# Sheet2.net
KiCad netlist of a schematic drawn in Altium Designer
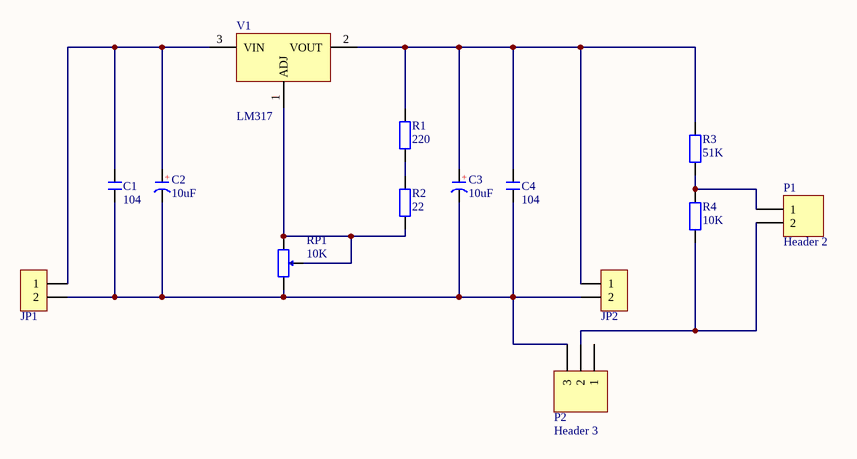
[diagram p0: Sheet2.SchDoc]

(export (version "E")
  (design (tool "Eeschema 10.0.6"))
  (components
    (comp (ref "C1")
      (value "104")
      (footprint "C 0805_M")
      (description "贴片电容")
      (libsource (lib "01 - 电容-电阻-电感") (part "C"))
    )
    (comp (ref "C2")
      (value "10uF")
      (footprint "CAP 2.0*5*11")
      (description "直插电解电容")
      (libsource (lib "01 - 电容-电阻-电感") (part "CE"))
    )
    (comp (ref "C3")
      (value "10uF")
      (footprint "CAP 2.0*5*11")
      (description "直插电解电容")
      (libsource (lib "01 - 电容-电阻-电感") (part "CE"))
    )
    (comp (ref "C4")
      (value "104")
      (footprint "C 0805_M")
      (description "贴片电容")
      (libsource (lib "01 - 电容-电阻-电感") (part "C"))
    )
    (comp (ref "JP1")
      (value "HDR-1X2")
      (footprint "KF2EDGK5.0-LI-2P")
      (description "2P接插件")
      (libsource (lib "") (part "Header 2_1"))
    )
    (comp (ref "JP2")
      (value "HDR-1X2")
      (footprint "KF2EDGK5.0-LI-2P")
      (description "2P接插件")
      (libsource (lib "21 - 接插件-脚距5.0mm") (part "Header 2"))
    )
    (comp (ref "P1")
      (value "Header 2")
      (footprint "HDR1X2")
      (description "Header, 2-Pin")
      (fields (field (name "PUBLISHER") "Altium Limited"))
      (libsource (lib "Miscellaneous Connectors") (part "Header 2"))
    )
    (comp (ref "P2")
      (value "Header 3")
      (footprint "HDR1X3")
      (description "Header, 3-Pin")
      (fields (field (name "PUBLISHER") "Altium Limited"))
      (libsource (lib "Miscellaneous Connectors") (part "Header 3"))
    )
    (comp (ref "R1")
      (value "220")
      (footprint "R 0805_M")
      (description "贴片电阻")
      (libsource (lib "01 - 电容-电阻-电感") (part "R"))
    )
    (comp (ref "R2")
      (value "22")
      (footprint "R 0805_M")
      (description "贴片电阻")
      (libsource (lib "01 - 电容-电阻-电感") (part "R"))
    )
    (comp (ref "R3")
      (value "51K")
      (footprint "R 0805_M")
      (description "贴片电阻")
      (libsource (lib "01 - 电容-电阻-电感") (part "R"))
    )
    (comp (ref "R4")
      (value "10K")
      (footprint "R 0805_M")
      (description "贴片电阻")
      (libsource (lib "01 - 电容-电阻-电感") (part "R"))
    )
    (comp (ref "RP1")
      (value "10K")
      (footprint "3296W")
      (description "单联电位器")
      (libsource (lib "01 - 电容-电阻-电感") (part "RP"))
    )
    (comp (ref "V1")
      (value "LM317")
      (footprint "TO220A")
      (description "可调线性稳压芯片")
      (libsource (lib "08 - 稳压芯片-电源管理芯片") (part "LM317"))
    )
  )
  (nets
    (net (code "1") (name "Net-(C2-A)") (class "Default")
      (node (ref "C1") (pin "2") (pinfunction "2_2") (pintype "passive"))
      (node (ref "C2") (pin "1") (pinfunction "A_1") (pintype "passive"))
      (node (ref "JP1") (pin "1") (pinfunction "1_1") (pintype "passive"))
      (node (ref "V1") (pin "3") (pinfunction "VIN_3") (pintype "passive"))
    )
    (net (code "2") (name "Net-(C2-K)") (class "Default")
      (node (ref "C1") (pin "1") (pinfunction "1_1") (pintype "passive"))
      (node (ref "C2") (pin "2") (pinfunction "K_2") (pintype "passive"))
      (node (ref "C3") (pin "2") (pinfunction "K_2") (pintype "passive"))
      (node (ref "C4") (pin "1") (pinfunction "1_1") (pintype "passive"))
      (node (ref "JP1") (pin "2") (pinfunction "2_2") (pintype "passive"))
      (node (ref "JP2") (pin "2") (pinfunction "2_2") (pintype "passive"))
      (node (ref "P2") (pin "3") (pinfunction "3_3") (pintype "passive"))
      (node (ref "RP1") (pin "3") (pinfunction "3_3") (pintype "passive"))
    )
    (net (code "3") (name "Net-(C3-A)") (class "Default")
      (node (ref "C3") (pin "1") (pinfunction "A_1") (pintype "passive"))
      (node (ref "C4") (pin "2") (pinfunction "2_2") (pintype "passive"))
      (node (ref "JP2") (pin "1") (pinfunction "1_1") (pintype "passive"))
      (node (ref "R1") (pin "2") (pinfunction "2_2") (pintype "passive"))
      (node (ref "R3") (pin "2") (pinfunction "2_2") (pintype "passive"))
      (node (ref "V1") (pin "2") (pinfunction "VOUT_2") (pintype "passive"))
    )
    (net (code "4") (name "Net-(P1-Pad1)") (class "Default")
      (node (ref "P1") (pin "1") (pinfunction "1_1") (pintype "passive"))
      (node (ref "R3") (pin "1") (pinfunction "1_1") (pintype "passive"))
      (node (ref "R4") (pin "2") (pinfunction "2_2") (pintype "passive"))
    )
    (net (code "5") (name "Net-(P1-Pad2)") (class "Default")
      (node (ref "P1") (pin "2") (pinfunction "2_2") (pintype "passive"))
      (node (ref "P2") (pin "2") (pinfunction "2_2") (pintype "passive"))
      (node (ref "R4") (pin "1") (pinfunction "1_1") (pintype "passive"))
    )
    (net (code "6") (name "Net-(R1-Pad1)") (class "Default")
      (node (ref "R1") (pin "1") (pinfunction "1_1") (pintype "passive"))
      (node (ref "R2") (pin "2") (pinfunction "2_2") (pintype "passive"))
    )
    (net (code "7") (name "Net-(V1-ADJ)") (class "Default")
      (node (ref "R2") (pin "1") (pinfunction "1_1") (pintype "passive"))
      (node (ref "RP1") (pin "1") (pinfunction "1_1") (pintype "passive"))
      (node (ref "RP1") (pin "2") (pinfunction "2_2") (pintype "passive"))
      (node (ref "V1") (pin "1") (pinfunction "ADJ_1") (pintype "passive"))
    )
    (net (code "8") (name "unconnected-(P2-Pad1)") (class "Default")
      (node (ref "P2") (pin "1") (pinfunction "1_1") (pintype "passive"))
    )
  )
)
